# esp8266-rfid.net
KiCad netlist of a schematic drawn in EAGLE
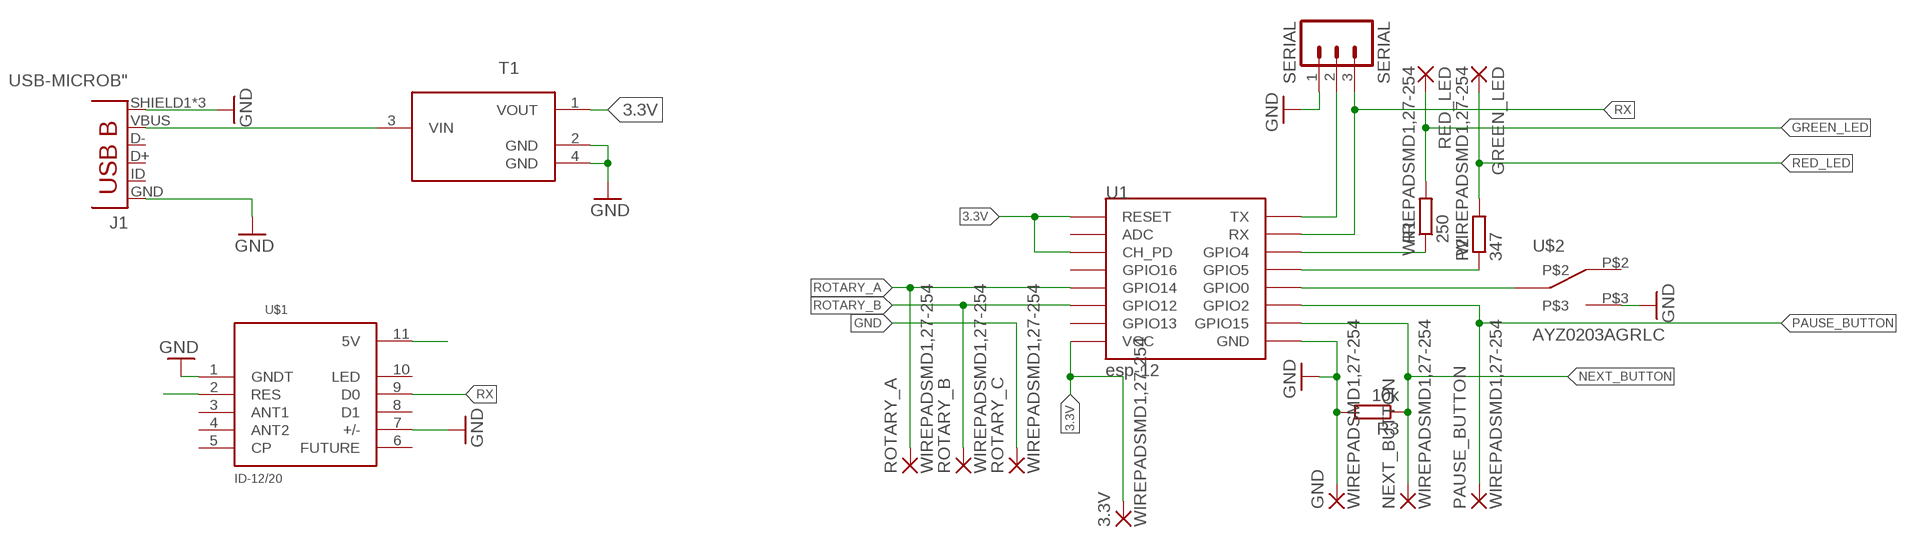
[diagram p0: schematic, sheet 1]

(export (version "E")
  (design (tool "Eeschema 10.0.6"))
  (components
    (comp (ref "3.3V")
      (value "WIREPADSMD1,27-254")
      (footprint "eagle-import:SMD1,27-2,54")
      (libsource (lib "eagle-import") (part "WIREPADSMD1,27-254"))
    )
    (comp (ref "GND")
      (value "WIREPADSMD1,27-254")
      (footprint "eagle-import:SMD1,27-2,54")
      (libsource (lib "eagle-import") (part "WIREPADSMD1,27-254"))
    )
    (comp (ref "GREEN_LED")
      (value "WIREPADSMD1,27-254")
      (footprint "eagle-import:SMD1,27-2,54")
      (libsource (lib "eagle-import") (part "WIREPADSMD1,27-254"))
    )
    (comp (ref "J1")
      (value "USB-MICROB\"")
      (footprint "eagle-import:USB-B-MICRO-SMD_V03")
      (libsource (lib "eagle-import") (part "USB-MICROB{dblquote}"))
    )
    (comp (ref "NEXT_BUTTON")
      (value "WIREPADSMD1,27-254")
      (footprint "eagle-import:SMD1,27-2,54")
      (libsource (lib "eagle-import") (part "WIREPADSMD1,27-254"))
    )
    (comp (ref "PAUSE_BUTTON")
      (value "WIREPADSMD1,27-254")
      (footprint "eagle-import:SMD1,27-2,54")
      (libsource (lib "eagle-import") (part "WIREPADSMD1,27-254"))
    )
    (comp (ref "R1")
      (value "250")
      (footprint "eagle-import:R0603")
      (libsource (lib "eagle-import") (part "R-EU_R0603"))
    )
    (comp (ref "R2")
      (value "347")
      (footprint "eagle-import:R0603")
      (libsource (lib "eagle-import") (part "R-EU_R0603"))
    )
    (comp (ref "R3")
      (value "10k")
      (footprint "eagle-import:R0603")
      (libsource (lib "eagle-import") (part "R-EU_R0603"))
    )
    (comp (ref "RED_LED")
      (value "WIREPADSMD1,27-254")
      (footprint "eagle-import:SMD1,27-2,54")
      (libsource (lib "eagle-import") (part "WIREPADSMD1,27-254"))
    )
    (comp (ref "ROTARY_A")
      (value "WIREPADSMD1,27-254")
      (footprint "eagle-import:SMD1,27-2,54")
      (libsource (lib "eagle-import") (part "WIREPADSMD1,27-254"))
    )
    (comp (ref "ROTARY_B")
      (value "WIREPADSMD1,27-254")
      (footprint "eagle-import:SMD1,27-2,54")
      (libsource (lib "eagle-import") (part "WIREPADSMD1,27-254"))
    )
    (comp (ref "ROTARY_C")
      (value "WIREPADSMD1,27-254")
      (footprint "eagle-import:SMD1,27-2,54")
      (libsource (lib "eagle-import") (part "WIREPADSMD1,27-254"))
    )
    (comp (ref "SERIAL")
      (value "SERIAL")
      (footprint "eagle-import:1X03")
      (libsource (lib "eagle-import") (part "M03PTH"))
    )
    (comp (ref "T1")
      (value "L78L33ACUTR")
      (footprint "eagle-import:SOT150P400X160-4N")
      (libsource (lib "eagle-import") (part "L78L33ACUTR"))
    )
    (comp (ref "U$1")
      (value "ID-12/20")
      (footprint "eagle-import:ID-12")
      (libsource (lib "eagle-import") (part "ID-12/20"))
    )
    (comp (ref "U$2")
      (value "AYZ0203AGRLC")
      (footprint "eagle-import:AYZ0203AGRLC")
      (libsource (lib "eagle-import") (part "AYZ0203AGRLC"))
    )
    (comp (ref "U1")
      (value "esp-12")
      (footprint "eagle-import:ESP12-SMD")
      (libsource (lib "eagle-import") (part "ESP12SMD"))
    )
  )
  (nets
    (net (code "1") (name "/VBUS") (class "Default")
      (node (ref "J1") (pin "VBUS") (pinfunction "VBUS_VBUS") (pintype "bidirectional"))
      (node (ref "T1") (pin "3") (pinfunction "VIN_3") (pintype "input"))
      (node (ref "U$1") (pin "11") (pinfunction "5V_11") (pintype "bidirectional"))
      (node (ref "U$1") (pin "2") (pinfunction "RES_2") (pintype "bidirectional"))
    )
    (net (code "2") (name "3.3V") (class "Default")
      (node (ref "3.3V") (pin "1") (pinfunction "P_1") (pintype "passive"))
      (node (ref "T1") (pin "1") (pinfunction "VOUT_1") (pintype "output"))
      (node (ref "U1") (pin "CH_PD") (pinfunction "CH_PD_CH_PD") (pintype "bidirectional"))
      (node (ref "U1") (pin "RESET") (pinfunction "RESET_RESET") (pintype "bidirectional"))
      (node (ref "U1") (pin "VCC") (pinfunction "VCC_VCC") (pintype "bidirectional"))
    )
    (net (code "3") (name "GND") (class "Default")
      (node (ref "GND") (pin "1") (pinfunction "P_1") (pintype "passive"))
      (node (ref "J1") (pin "GND") (pinfunction "GND_GND") (pintype "bidirectional"))
      (node (ref "J1") (pin "SHIELD1") (pinfunction "SHIELD_SHIELD1") (pintype "bidirectional"))
      (node (ref "J1") (pin "SHIELD2") (pinfunction "SHIELD_SHIELD2") (pintype "bidirectional"))
      (node (ref "J1") (pin "SHIELD3") (pinfunction "SHIELD_SHIELD3") (pintype "bidirectional"))
      (node (ref "R3") (pin "2") (pinfunction "2_2") (pintype "passive"))
      (node (ref "ROTARY_C") (pin "1") (pinfunction "P_1") (pintype "passive"))
      (node (ref "SERIAL") (pin "1") (pinfunction "1_1") (pintype "passive"))
      (node (ref "T1") (pin "2") (pinfunction "GND_2") (pintype "power_in"))
      (node (ref "T1") (pin "4") (pinfunction "GND_4") (pintype "power_in"))
      (node (ref "U$1") (pin "1") (pinfunction "GNDT_1") (pintype "bidirectional"))
      (node (ref "U$1") (pin "7") (pinfunction "+/-_7") (pintype "bidirectional"))
      (node (ref "U$2") (pin "P$3") (pinfunction "P$3_P$3") (pintype "bidirectional"))
      (node (ref "U1") (pin "GND") (pinfunction "GND_GND") (pintype "bidirectional"))
    )
    (net (code "4") (name "GREEN_LED") (class "Default")
      (node (ref "R1") (pin "2") (pinfunction "2_2") (pintype "passive"))
      (node (ref "RED_LED") (pin "1") (pinfunction "P_1") (pintype "passive"))
    )
    (net (code "5") (name "NEXT_BUTTON") (class "Default")
      (node (ref "NEXT_BUTTON") (pin "1") (pinfunction "P_1") (pintype "passive"))
      (node (ref "R3") (pin "1") (pinfunction "1_1") (pintype "passive"))
      (node (ref "U1") (pin "GPIO15") (pinfunction "GPIO15_GPIO15") (pintype "bidirectional"))
    )
    (net (code "6") (name "Net-(R1-Pad1)") (class "Default")
      (node (ref "R1") (pin "1") (pinfunction "1_1") (pintype "passive"))
      (node (ref "U1") (pin "GPIO4") (pinfunction "GPIO4_GPIO4") (pintype "bidirectional"))
    )
    (net (code "7") (name "Net-(R2-Pad1)") (class "Default")
      (node (ref "R2") (pin "1") (pinfunction "1_1") (pintype "passive"))
      (node (ref "U1") (pin "GPIO5") (pinfunction "GPIO5_GPIO5") (pintype "bidirectional"))
    )
    (net (code "8") (name "Net-(U$2-COM)") (class "Default")
      (node (ref "U$2") (pin "P$1") (pinfunction "COM_P$1") (pintype "bidirectional"))
      (node (ref "U1") (pin "GPIO0") (pinfunction "GPIO0_GPIO0") (pintype "bidirectional"))
    )
    (net (code "9") (name "Net-(U1-TX)") (class "Default")
      (node (ref "SERIAL") (pin "2") (pinfunction "2_2") (pintype "passive"))
      (node (ref "U1") (pin "TXD0") (pinfunction "TX_TXD0") (pintype "bidirectional"))
    )
    (net (code "10") (name "PAUSE_BUTTON") (class "Default")
      (node (ref "PAUSE_BUTTON") (pin "1") (pinfunction "P_1") (pintype "passive"))
      (node (ref "U1") (pin "GPIO2") (pinfunction "GPIO2_GPIO2") (pintype "bidirectional"))
    )
    (net (code "11") (name "RED_LED") (class "Default")
      (node (ref "GREEN_LED") (pin "1") (pinfunction "P_1") (pintype "passive"))
      (node (ref "R2") (pin "2") (pinfunction "2_2") (pintype "passive"))
    )
    (net (code "12") (name "ROTARY_A") (class "Default")
      (node (ref "ROTARY_A") (pin "1") (pinfunction "P_1") (pintype "passive"))
      (node (ref "U1") (pin "GPIO14") (pinfunction "GPIO14_GPIO14") (pintype "bidirectional"))
    )
    (net (code "13") (name "ROTARY_B") (class "Default")
      (node (ref "ROTARY_B") (pin "1") (pinfunction "P_1") (pintype "passive"))
      (node (ref "U1") (pin "GPIO12") (pinfunction "GPIO12_GPIO12") (pintype "bidirectional"))
    )
    (net (code "14") (name "RX") (class "Default")
      (node (ref "SERIAL") (pin "3") (pinfunction "3_3") (pintype "passive"))
      (node (ref "U$1") (pin "9") (pinfunction "D0_9") (pintype "bidirectional"))
      (node (ref "U1") (pin "RXD0") (pinfunction "RX_RXD0") (pintype "bidirectional"))
    )
    (net (code "15") (name "unconnected-(J1-PadD+)") (class "Default")
      (node (ref "J1") (pin "D+") (pinfunction "D+_D+") (pintype "bidirectional"))
    )
    (net (code "16") (name "unconnected-(J1-PadD-)") (class "Default")
      (node (ref "J1") (pin "D-") (pinfunction "D-_D-") (pintype "bidirectional"))
    )
    (net (code "17") (name "unconnected-(J1-USBID-PadID)") (class "Default")
      (node (ref "J1") (pin "ID") (pinfunction "USBID_ID") (pintype "bidirectional"))
    )
    (net (code "18") (name "unconnected-(U$1-ANT1-Pad3)") (class "Default")
      (node (ref "U$1") (pin "3") (pinfunction "ANT1_3") (pintype "bidirectional"))
    )
    (net (code "19") (name "unconnected-(U$1-ANT2-Pad4)") (class "Default")
      (node (ref "U$1") (pin "4") (pinfunction "ANT2_4") (pintype "bidirectional"))
    )
    (net (code "20") (name "unconnected-(U$1-CP-Pad5)") (class "Default")
      (node (ref "U$1") (pin "5") (pinfunction "CP_5") (pintype "bidirectional"))
    )
    (net (code "21") (name "unconnected-(U$1-D1-Pad8)") (class "Default")
      (node (ref "U$1") (pin "8") (pinfunction "D1_8") (pintype "bidirectional"))
    )
    (net (code "22") (name "unconnected-(U$1-FUTURE-Pad6)") (class "Default")
      (node (ref "U$1") (pin "6") (pinfunction "FUTURE_6") (pintype "bidirectional"))
    )
    (net (code "23") (name "unconnected-(U$1-LED-Pad10)") (class "Default")
      (node (ref "U$1") (pin "10") (pinfunction "LED_10") (pintype "bidirectional"))
    )
    (net (code "24") (name "unconnected-(U$2-PadP$2)") (class "Default")
      (node (ref "U$2") (pin "P$2") (pinfunction "P$2_P$2") (pintype "bidirectional"))
    )
    (net (code "25") (name "unconnected-(U1-PadADC)") (class "Default")
      (node (ref "U1") (pin "ADC") (pinfunction "ADC_ADC") (pintype "bidirectional"))
    )
    (net (code "26") (name "unconnected-(U1-PadGPIO13)") (class "Default")
      (node (ref "U1") (pin "GPIO13") (pinfunction "GPIO13_GPIO13") (pintype "bidirectional"))
    )
    (net (code "27") (name "unconnected-(U1-PadGPIO16)") (class "Default")
      (node (ref "U1") (pin "GPIO16") (pinfunction "GPIO16_GPIO16") (pintype "bidirectional"))
    )
  )
)
